# LPCB220_-_DAC_B.net
KiCad netlist of a schematic drawn in Altium Designer
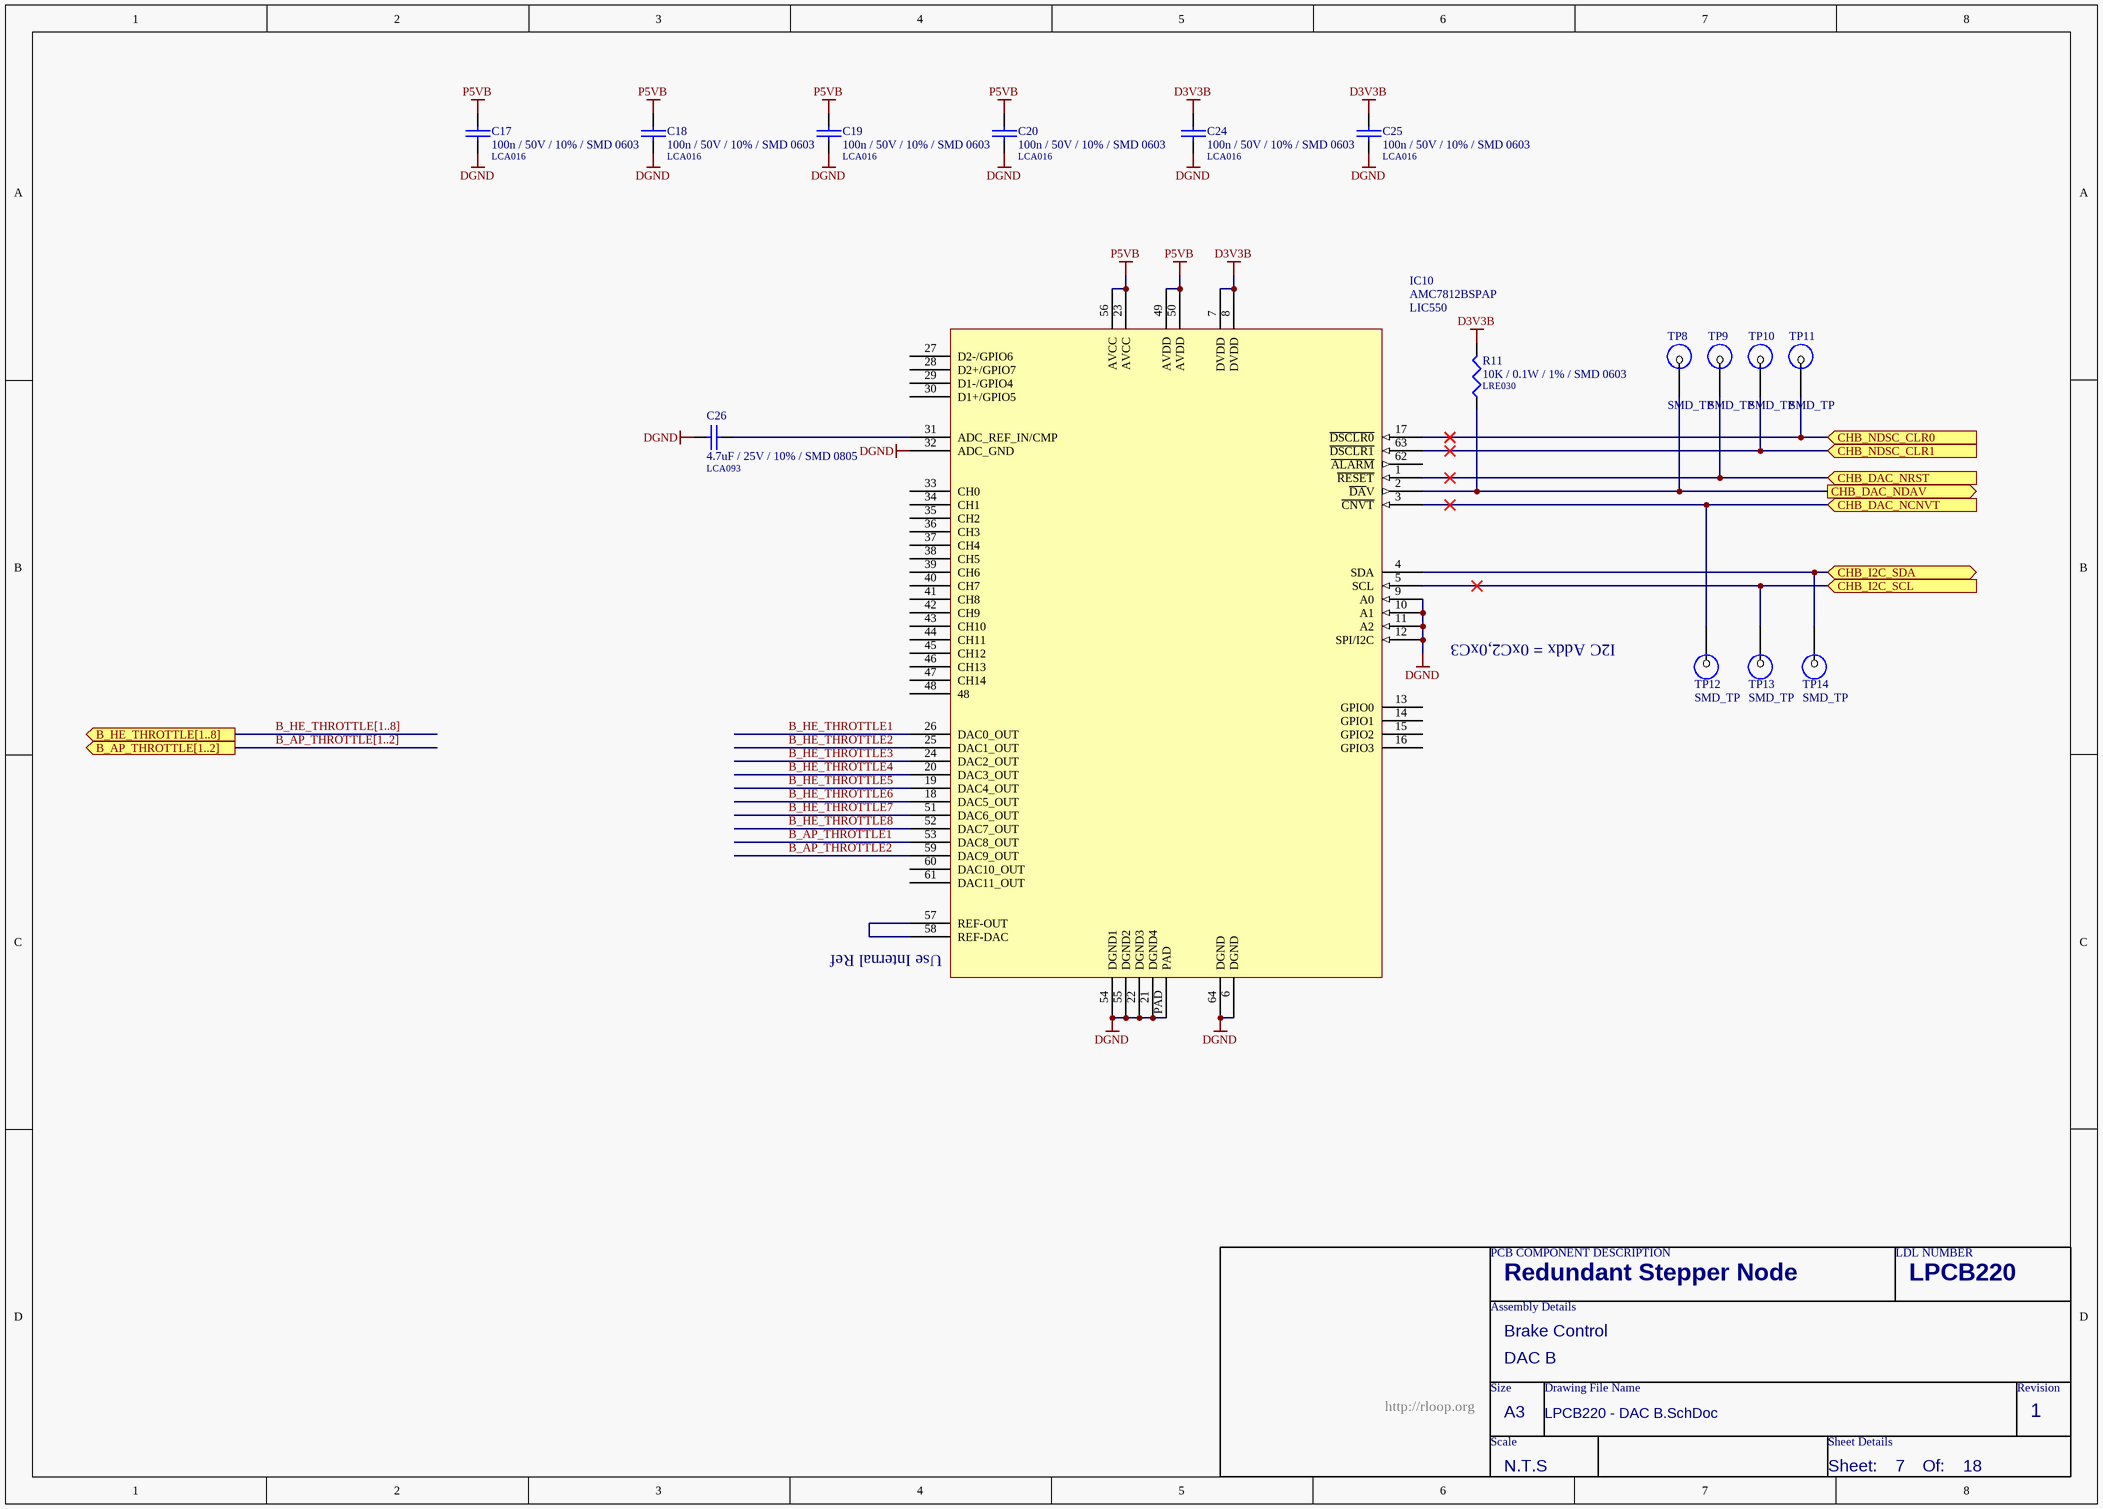
[diagram p0: LPCB220 - DAC B.SchDoc]

(export (version "E")
  (design (tool "Eeschema 10.0.6"))
  (components
    (comp (ref "C17")
      (value "100n / 50V / 10% / SMD 0603")
      (footprint "LFP011__CC1608-0603-IPC7351_B")
      (description "Capacitor, Ceramic Chip, 100nF (0.1uF), 50V, 5%, SMD 0603 [LCA016]")
      (fields (field (name "LDL_NUMBER") "LCA016"))
      (libsource (lib "LDL_Capacitors") (part "100n / 50V / 10% / SMD 0603"))
    )
    (comp (ref "C18")
      (value "100n / 50V / 10% / SMD 0603")
      (footprint "LFP011__CC1608-0603-IPC7351_B")
      (description "Capacitor, Ceramic Chip, 100nF (0.1uF), 50V, 5%, SMD 0603 [LCA016]")
      (fields (field (name "LDL_NUMBER") "LCA016"))
      (libsource (lib "LDL_Capacitors") (part "100n / 50V / 10% / SMD 0603"))
    )
    (comp (ref "C19")
      (value "100n / 50V / 10% / SMD 0603")
      (footprint "LFP011__CC1608-0603-IPC7351_B")
      (description "Capacitor, Ceramic Chip, 100nF (0.1uF), 50V, 5%, SMD 0603 [LCA016]")
      (fields (field (name "LDL_NUMBER") "LCA016"))
      (libsource (lib "LDL_Capacitors") (part "100n / 50V / 10% / SMD 0603"))
    )
    (comp (ref "C20")
      (value "100n / 50V / 10% / SMD 0603")
      (footprint "LFP011__CC1608-0603-IPC7351_B")
      (description "Capacitor, Ceramic Chip, 100nF (0.1uF), 50V, 5%, SMD 0603 [LCA016]")
      (fields (field (name "LDL_NUMBER") "LCA016"))
      (libsource (lib "LDL_Capacitors") (part "100n / 50V / 10% / SMD 0603"))
    )
    (comp (ref "C24")
      (value "100n / 50V / 10% / SMD 0603")
      (footprint "LFP011__CC1608-0603-IPC7351_B")
      (description "Capacitor, Ceramic Chip, 100nF (0.1uF), 50V, 5%, SMD 0603 [LCA016]")
      (fields (field (name "LDL_NUMBER") "LCA016"))
      (libsource (lib "LDL_Capacitors") (part "100n / 50V / 10% / SMD 0603"))
    )
    (comp (ref "C25")
      (value "100n / 50V / 10% / SMD 0603")
      (footprint "LFP011__CC1608-0603-IPC7351_B")
      (description "Capacitor, Ceramic Chip, 100nF (0.1uF), 50V, 5%, SMD 0603 [LCA016]")
      (fields (field (name "LDL_NUMBER") "LCA016"))
      (libsource (lib "LDL_Capacitors") (part "100n / 50V / 10% / SMD 0603"))
    )
    (comp (ref "C26")
      (value "4.7uF / 25V / 10% / SMD 0805")
      (footprint "LFP010__CC2012-0805-IPC7351_B")
      (description "Capacitor, Ceramic Chip, 4.7uF, 25V, 10%, SMD 0805 [LCA093]")
      (fields (field (name "LDL_NUMBER") "LCA093"))
      (libsource (lib "LDL_Capacitors") (part "4.7uF / 25V / 10% / SMD 0805"))
    )
    (comp (ref "IC10")
      (value "AMC7812BSPAP")
      (footprint "LFP134__H-QFP10X10-64N")
      (description "IC, ADC / DAC, SMD [LIC550]")
      (fields (field (name "LDL_NUMBER") "LIC550"))
      (libsource (lib "LDL_Semiconductors") (part "AMC7812BSPAP"))
    )
    (comp (ref "R11")
      (value "10K / 0.1W / 1% / SMD 0603")
      (footprint "LFP020__CR1608-0603-IPC7351_B")
      (description "Resistor, Ceramic Chip, 10K, 0.1W, 1%, SMD 0603 [LRE030]")
      (fields (field (name "LDL_NUMBER") "LRE030"))
      (libsource (lib "LDL_Resistors") (part "10K / 0.1W / 1% / SMD 0603"))
    )
    (comp (ref "TP8")
      (value "SMD_TP")
      (footprint "SMD-TP")
      (description "SMD Test Point")
      (libsource (lib "LDL_Connectors") (part "SMD_TP"))
    )
    (comp (ref "TP9")
      (value "SMD_TP")
      (footprint "SMD-TP")
      (description "SMD Test Point")
      (libsource (lib "LDL_Connectors") (part "SMD_TP"))
    )
    (comp (ref "TP10")
      (value "SMD_TP")
      (footprint "SMD-TP")
      (description "SMD Test Point")
      (libsource (lib "LDL_Connectors") (part "SMD_TP"))
    )
    (comp (ref "TP11")
      (value "SMD_TP")
      (footprint "SMD-TP")
      (description "SMD Test Point")
      (libsource (lib "LDL_Connectors") (part "SMD_TP"))
    )
    (comp (ref "TP12")
      (value "SMD_TP")
      (footprint "SMD-TP")
      (description "SMD Test Point")
      (libsource (lib "LDL_Connectors") (part "SMD_TP"))
    )
    (comp (ref "TP13")
      (value "SMD_TP")
      (footprint "SMD-TP")
      (description "SMD Test Point")
      (libsource (lib "LDL_Connectors") (part "SMD_TP"))
    )
    (comp (ref "TP14")
      (value "SMD_TP")
      (footprint "SMD-TP")
      (description "SMD Test Point")
      (libsource (lib "LDL_Connectors") (part "SMD_TP"))
    )
  )
  (nets
    (net (code "1") (name "/B_AP_THROTTLE1") (class "Default")
      (node (ref "IC10") (pin "53") (pinfunction "DAC8_OUT_53") (pintype "passive"))
    )
    (net (code "2") (name "/B_AP_THROTTLE2") (class "Default")
      (node (ref "IC10") (pin "59") (pinfunction "DAC9_OUT_59") (pintype "passive"))
    )
    (net (code "4") (name "/B_HE_THROTTLE1") (class "Default")
      (node (ref "IC10") (pin "26") (pinfunction "DAC0_OUT_26") (pintype "passive"))
    )
    (net (code "5") (name "/B_HE_THROTTLE2") (class "Default")
      (node (ref "IC10") (pin "25") (pinfunction "DAC1_OUT_25") (pintype "passive"))
    )
    (net (code "6") (name "/B_HE_THROTTLE3") (class "Default")
      (node (ref "IC10") (pin "24") (pinfunction "DAC2_OUT_24") (pintype "passive"))
    )
    (net (code "7") (name "/B_HE_THROTTLE4") (class "Default")
      (node (ref "IC10") (pin "20") (pinfunction "DAC3_OUT_20") (pintype "passive"))
    )
    (net (code "8") (name "/B_HE_THROTTLE5") (class "Default")
      (node (ref "IC10") (pin "19") (pinfunction "DAC4_OUT_19") (pintype "passive"))
    )
    (net (code "9") (name "/B_HE_THROTTLE6") (class "Default")
      (node (ref "IC10") (pin "18") (pinfunction "DAC5_OUT_18") (pintype "passive"))
    )
    (net (code "10") (name "/B_HE_THROTTLE7") (class "Default")
      (node (ref "IC10") (pin "51") (pinfunction "DAC6_OUT_51") (pintype "passive"))
    )
    (net (code "11") (name "/B_HE_THROTTLE8") (class "Default")
      (node (ref "IC10") (pin "52") (pinfunction "DAC7_OUT_52") (pintype "passive"))
    )
    (net (code "13") (name "/CHB_DAC_NCNVT") (class "Default")
      (node (ref "IC10") (pin "3") (pinfunction "~{CNVT}_3") (pintype "input"))
      (node (ref "TP12") (pin "1") (pintype "passive"))
    )
    (net (code "14") (name "/CHB_DAC_NDAV") (class "Default")
      (node (ref "IC10") (pin "2") (pinfunction "~{DA}V_2") (pintype "output"))
      (node (ref "R11") (pin "1") (pintype "passive"))
      (node (ref "TP8") (pin "1") (pintype "passive"))
    )
    (net (code "15") (name "/CHB_DAC_NRST") (class "Default")
      (node (ref "IC10") (pin "1") (pinfunction "~{RESET}_1") (pintype "input"))
      (node (ref "TP9") (pin "1") (pintype "passive"))
    )
    (net (code "16") (name "/CHB_I2C_SCL") (class "Default")
      (node (ref "IC10") (pin "5") (pinfunction "SCL_5") (pintype "input"))
      (node (ref "TP13") (pin "1") (pintype "passive"))
    )
    (net (code "17") (name "/CHB_I2C_SDA") (class "Default")
      (node (ref "IC10") (pin "4") (pinfunction "SDA_4") (pintype "passive"))
      (node (ref "TP14") (pin "1") (pintype "passive"))
    )
    (net (code "18") (name "/CHB_NDSC_CLR0") (class "Default")
      (node (ref "IC10") (pin "17") (pinfunction "~{DSCLR0}_17") (pintype "input"))
      (node (ref "TP11") (pin "1") (pintype "passive"))
    )
    (net (code "19") (name "/CHB_NDSC_CLR1") (class "Default")
      (node (ref "IC10") (pin "63") (pinfunction "~{DSCLR1}_63") (pintype "input"))
      (node (ref "TP10") (pin "1") (pintype "passive"))
    )
    (net (code "20") (name "D3V3B") (class "Default")
      (node (ref "C24") (pin "1") (pintype "passive"))
      (node (ref "C25") (pin "1") (pintype "passive"))
      (node (ref "IC10") (pin "7") (pinfunction "DVDD_7") (pintype "power_in"))
      (node (ref "IC10") (pin "8") (pinfunction "DVDD_8") (pintype "power_in"))
      (node (ref "R11") (pin "2") (pintype "passive"))
    )
    (net (code "21") (name "DGND") (class "Default")
      (node (ref "C17") (pin "2") (pintype "passive"))
      (node (ref "C18") (pin "2") (pintype "passive"))
      (node (ref "C19") (pin "2") (pintype "passive"))
      (node (ref "C20") (pin "2") (pintype "passive"))
      (node (ref "C24") (pin "2") (pintype "passive"))
      (node (ref "C25") (pin "2") (pintype "passive"))
      (node (ref "C26") (pin "1") (pintype "passive"))
      (node (ref "IC10") (pin "10") (pinfunction "A1_10") (pintype "input"))
      (node (ref "IC10") (pin "11") (pinfunction "A2_11") (pintype "input"))
      (node (ref "IC10") (pin "12") (pinfunction "SPI/I2C_12") (pintype "input"))
      (node (ref "IC10") (pin "21") (pinfunction "DGND4_21") (pintype "power_in"))
      (node (ref "IC10") (pin "22") (pinfunction "DGND3_22") (pintype "power_in"))
      (node (ref "IC10") (pin "32") (pinfunction "ADC_GND_32") (pintype "power_in"))
      (node (ref "IC10") (pin "54") (pinfunction "DGND1_54") (pintype "power_in"))
      (node (ref "IC10") (pin "55") (pinfunction "DGND2_55") (pintype "power_in"))
      (node (ref "IC10") (pin "6") (pinfunction "DGND_6") (pintype "power_in"))
      (node (ref "IC10") (pin "64") (pinfunction "DGND_64") (pintype "power_in"))
      (node (ref "IC10") (pin "9") (pinfunction "A0_9") (pintype "input"))
      (node (ref "IC10") (pin "PAD") (pinfunction "PAD_PAD") (pintype "power_in"))
    )
    (net (code "22") (name "Net-(IC10-ADC_REF_IN{slash}CMP)") (class "Default")
      (node (ref "C26") (pin "2") (pintype "passive"))
      (node (ref "IC10") (pin "31") (pinfunction "ADC_REF_IN/CMP_31") (pintype "passive"))
    )
    (net (code "23") (name "Net-(IC10-REF-DAC)") (class "Default")
      (node (ref "IC10") (pin "57") (pinfunction "REF-OUT_57") (pintype "passive"))
      (node (ref "IC10") (pin "58") (pinfunction "REF-DAC_58") (pintype "passive"))
    )
    (net (code "24") (name "P5VB") (class "Default")
      (node (ref "C17") (pin "1") (pintype "passive"))
      (node (ref "C18") (pin "1") (pintype "passive"))
      (node (ref "C19") (pin "1") (pintype "passive"))
      (node (ref "C20") (pin "1") (pintype "passive"))
      (node (ref "IC10") (pin "23") (pinfunction "AVCC_23") (pintype "power_in"))
      (node (ref "IC10") (pin "49") (pinfunction "AVDD_49") (pintype "power_in"))
      (node (ref "IC10") (pin "50") (pinfunction "AVDD_50") (pintype "power_in"))
      (node (ref "IC10") (pin "56") (pinfunction "AVCC_56") (pintype "power_in"))
    )
    (net (code "25") (name "unconnected-(IC10-CH0-Pad33)") (class "Default")
      (node (ref "IC10") (pin "33") (pinfunction "CH0_33") (pintype "passive"))
    )
    (net (code "26") (name "unconnected-(IC10-CH1-Pad34)") (class "Default")
      (node (ref "IC10") (pin "34") (pinfunction "CH1_34") (pintype "passive"))
    )
    (net (code "27") (name "unconnected-(IC10-CH2-Pad35)") (class "Default")
      (node (ref "IC10") (pin "35") (pinfunction "CH2_35") (pintype "passive"))
    )
    (net (code "28") (name "unconnected-(IC10-CH3-Pad36)") (class "Default")
      (node (ref "IC10") (pin "36") (pinfunction "CH3_36") (pintype "passive"))
    )
    (net (code "29") (name "unconnected-(IC10-CH4-Pad37)") (class "Default")
      (node (ref "IC10") (pin "37") (pinfunction "CH4_37") (pintype "passive"))
    )
    (net (code "30") (name "unconnected-(IC10-CH5-Pad38)") (class "Default")
      (node (ref "IC10") (pin "38") (pinfunction "CH5_38") (pintype "passive"))
    )
    (net (code "31") (name "unconnected-(IC10-CH6-Pad39)") (class "Default")
      (node (ref "IC10") (pin "39") (pinfunction "CH6_39") (pintype "passive"))
    )
    (net (code "32") (name "unconnected-(IC10-CH7-Pad40)") (class "Default")
      (node (ref "IC10") (pin "40") (pinfunction "CH7_40") (pintype "passive"))
    )
    (net (code "33") (name "unconnected-(IC10-CH8-Pad41)") (class "Default")
      (node (ref "IC10") (pin "41") (pinfunction "CH8_41") (pintype "passive"))
    )
    (net (code "34") (name "unconnected-(IC10-CH9-Pad42)") (class "Default")
      (node (ref "IC10") (pin "42") (pinfunction "CH9_42") (pintype "passive"))
    )
    (net (code "35") (name "unconnected-(IC10-CH10-Pad43)") (class "Default")
      (node (ref "IC10") (pin "43") (pinfunction "CH10_43") (pintype "passive"))
    )
    (net (code "36") (name "unconnected-(IC10-CH11-Pad44)") (class "Default")
      (node (ref "IC10") (pin "44") (pinfunction "CH11_44") (pintype "passive"))
    )
    (net (code "37") (name "unconnected-(IC10-CH12-Pad45)") (class "Default")
      (node (ref "IC10") (pin "45") (pinfunction "CH12_45") (pintype "passive"))
    )
    (net (code "38") (name "unconnected-(IC10-CH13-Pad46)") (class "Default")
      (node (ref "IC10") (pin "46") (pinfunction "CH13_46") (pintype "passive"))
    )
    (net (code "39") (name "unconnected-(IC10-CH14-Pad47)") (class "Default")
      (node (ref "IC10") (pin "47") (pinfunction "CH14_47") (pintype "passive"))
    )
    (net (code "40") (name "unconnected-(IC10-D1+{slash}GPIO5-Pad30)") (class "Default")
      (node (ref "IC10") (pin "30") (pinfunction "D1+/GPIO5_30") (pintype "passive"))
    )
    (net (code "41") (name "unconnected-(IC10-D1-{slash}GPIO4-Pad29)") (class "Default")
      (node (ref "IC10") (pin "29") (pinfunction "D1-/GPIO4_29") (pintype "passive"))
    )
    (net (code "42") (name "unconnected-(IC10-D2+{slash}GPIO7-Pad28)") (class "Default")
      (node (ref "IC10") (pin "28") (pinfunction "D2+/GPIO7_28") (pintype "passive"))
    )
    (net (code "43") (name "unconnected-(IC10-D2-{slash}GPIO6-Pad27)") (class "Default")
      (node (ref "IC10") (pin "27") (pinfunction "D2-/GPIO6_27") (pintype "passive"))
    )
    (net (code "44") (name "unconnected-(IC10-DAC10_OUT-Pad60)") (class "Default")
      (node (ref "IC10") (pin "60") (pinfunction "DAC10_OUT_60") (pintype "passive"))
    )
    (net (code "45") (name "unconnected-(IC10-DAC11_OUT-Pad61)") (class "Default")
      (node (ref "IC10") (pin "61") (pinfunction "DAC11_OUT_61") (pintype "passive"))
    )
    (net (code "46") (name "unconnected-(IC10-GPIO0-Pad13)") (class "Default")
      (node (ref "IC10") (pin "13") (pinfunction "GPIO0_13") (pintype "passive"))
    )
    (net (code "47") (name "unconnected-(IC10-GPIO1-Pad14)") (class "Default")
      (node (ref "IC10") (pin "14") (pinfunction "GPIO1_14") (pintype "passive"))
    )
    (net (code "48") (name "unconnected-(IC10-GPIO2-Pad15)") (class "Default")
      (node (ref "IC10") (pin "15") (pinfunction "GPIO2_15") (pintype "passive"))
    )
    (net (code "49") (name "unconnected-(IC10-GPIO3-Pad16)") (class "Default")
      (node (ref "IC10") (pin "16") (pinfunction "GPIO3_16") (pintype "passive"))
    )
    (net (code "50") (name "unconnected-(IC10-Pad48)") (class "Default")
      (node (ref "IC10") (pin "48") (pinfunction "48_48") (pintype "passive"))
    )
    (net (code "51") (name "unconnected-(IC10-~{ALARM}-Pad62)") (class "Default")
      (node (ref "IC10") (pin "62") (pinfunction "~{ALARM}_62") (pintype "output"))
    )
  )
)
